# OpenTCUSandwich.net
KiCad netlist of a schematic drawn in EasyEDA
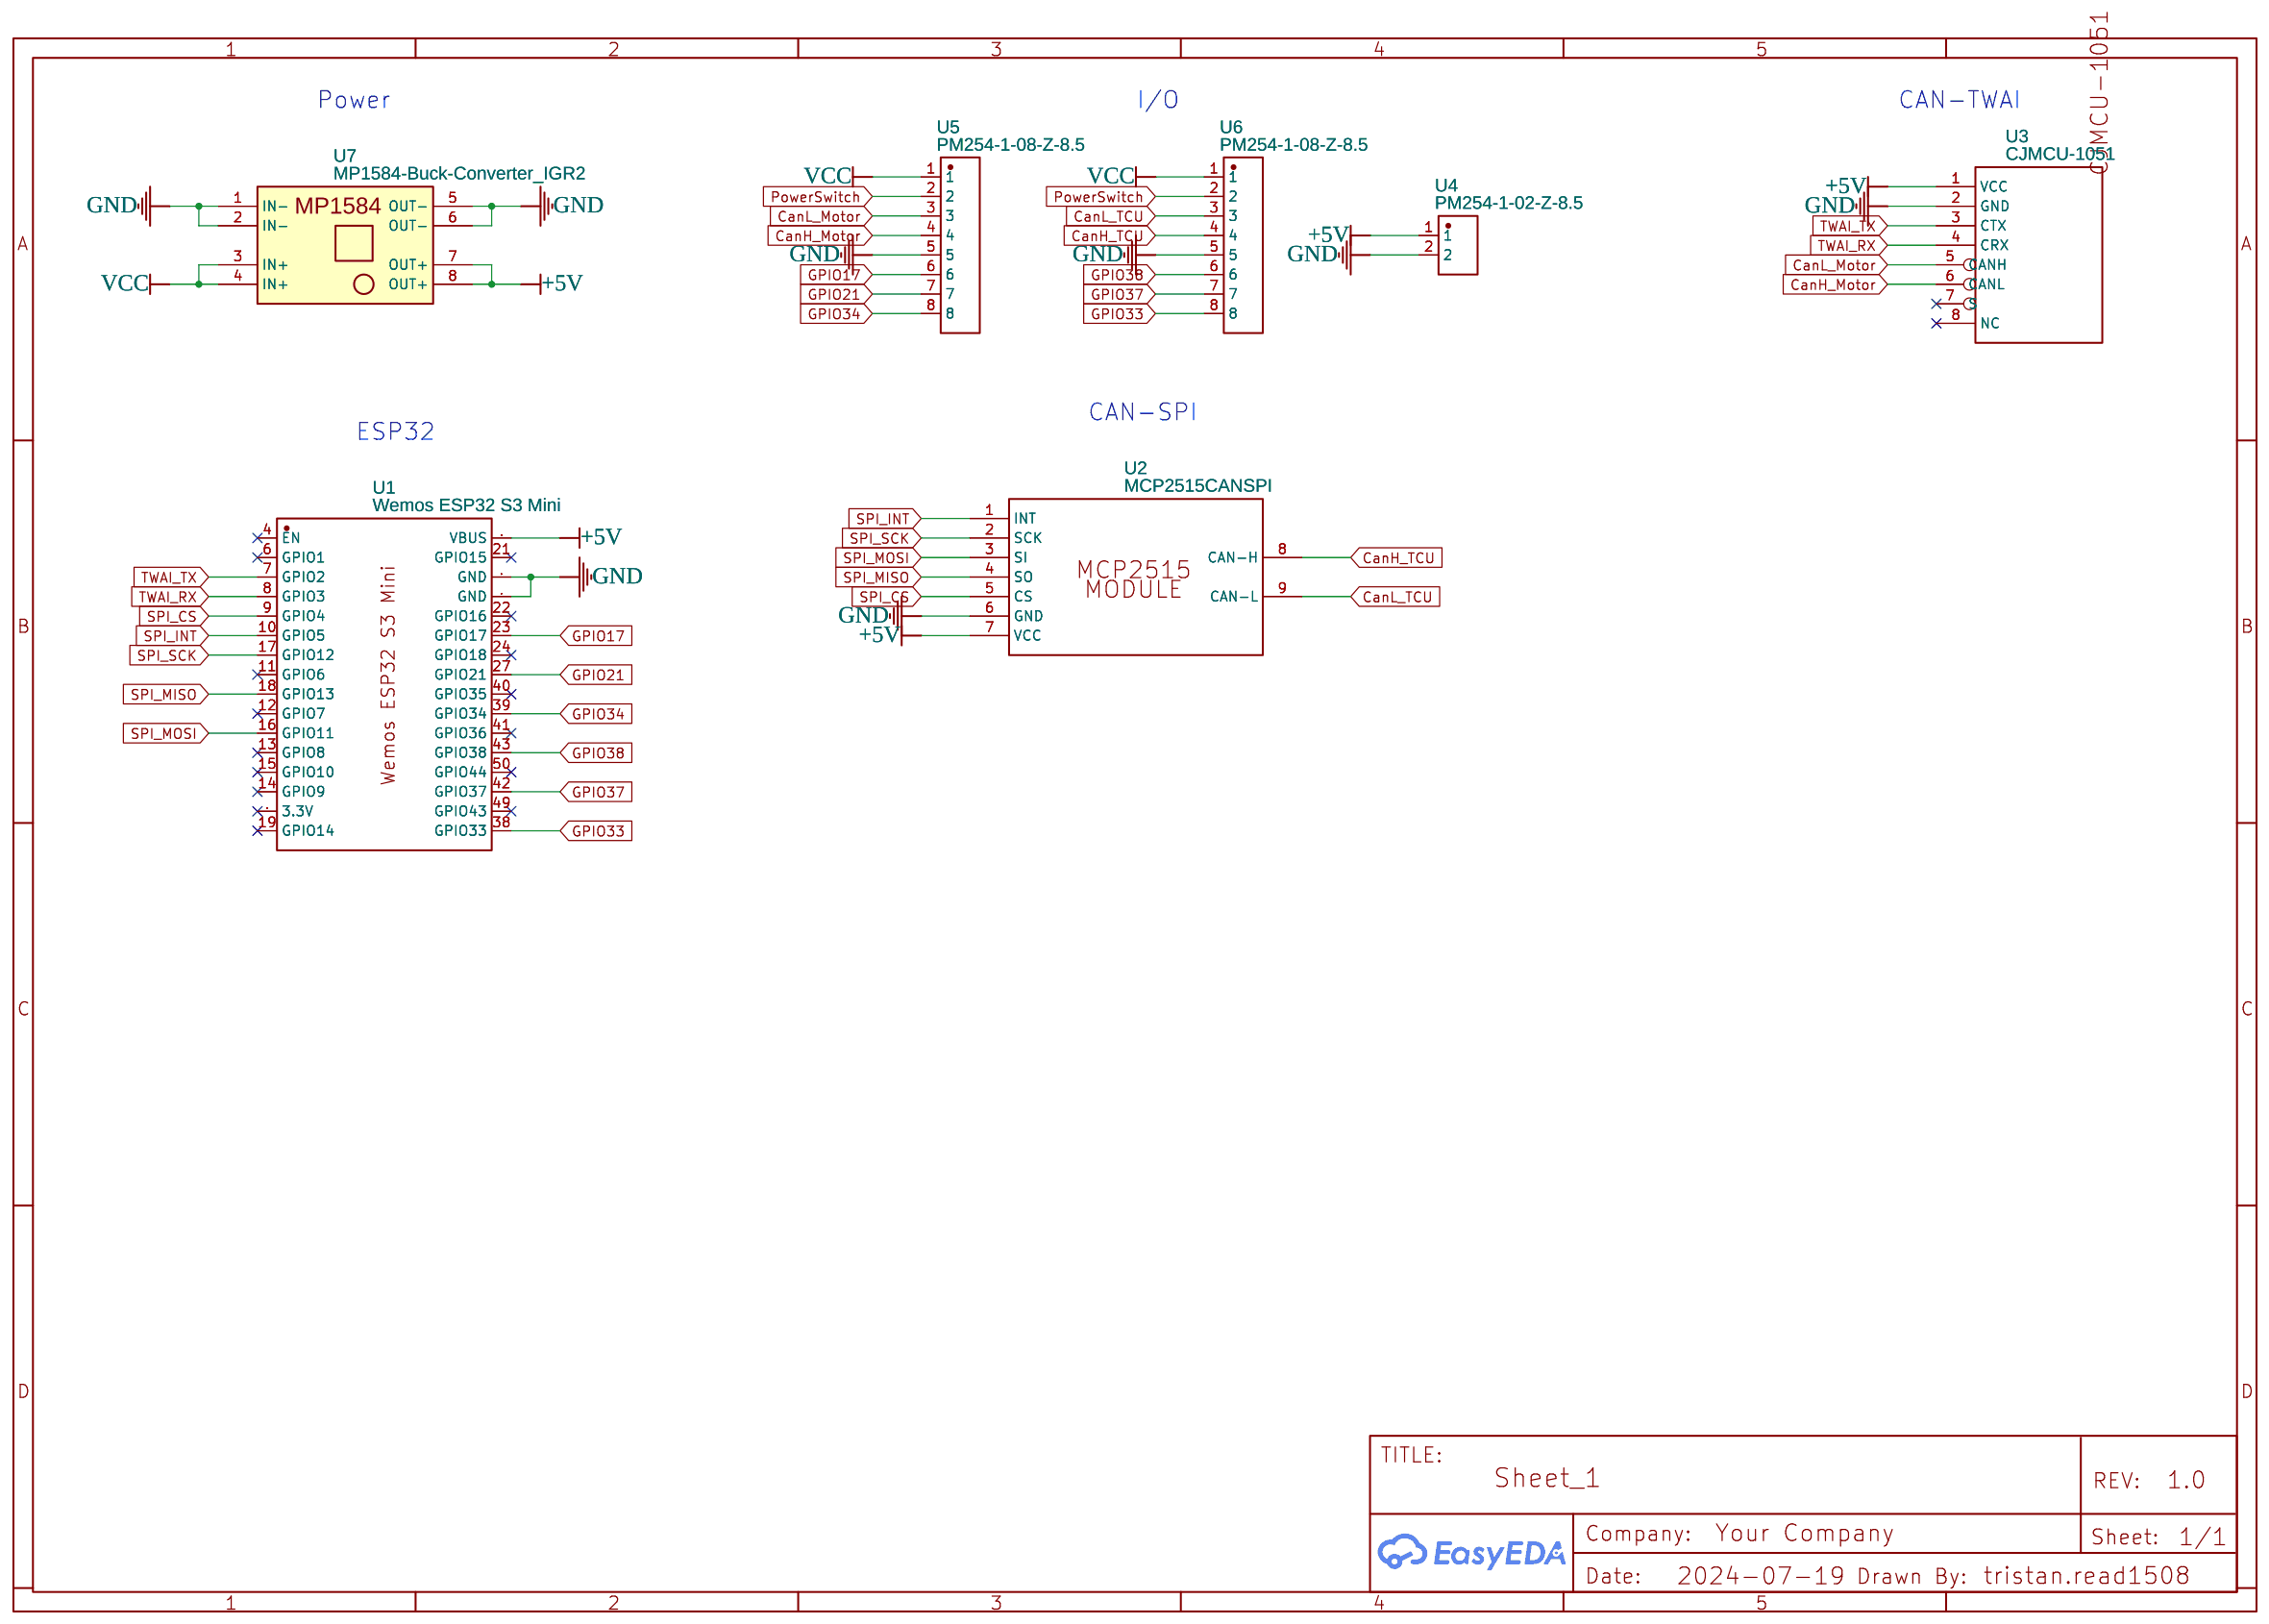
[diagram p0: schematic sheet]

(export (version "E")
  (design (tool "Eeschema 10.0.6"))
  (components
    (comp (ref "U1")
      (value "Wemos ESP32 S3 Mini")
      (fields (field (name "Manufacturer") "Wemos"))
      (libsource (lib "") (part "Wemos ESP32 S3 Mini"))
    )
    (comp (ref "U2") (value "MCP2515CANSPI") (libsource (lib "") (part "MCP2515CANSPI")))
    (comp (ref "U3") (value "CJMCU-1051") (libsource (lib "") (part "CJMCU-1051")))
    (comp (ref "U4")
      (value "PM254-1-02-Z-8.5")
      (fields (field (name "Manufacturer") "HCTL(华灿天禄)"))
      (libsource (lib "") (part "PM254-1-02-Z-8.5"))
    )
    (comp (ref "U5")
      (value "PM254-1-08-Z-8.5")
      (fields (field (name "Manufacturer") "HCTL(华灿天禄)"))
      (libsource (lib "") (part "PM254-1-08-Z-8.5"))
    )
    (comp (ref "U6")
      (value "PM254-1-08-Z-8.5")
      (fields (field (name "Manufacturer") "HCTL(华灿天禄)"))
      (libsource (lib "") (part "PM254-1-08-Z-8.5"))
    )
    (comp (ref "U7")
      (value "MP1584-Buck-Converter_IGR2")
      (fields (field (name "Manufacturer Part") "MP1584EN"))
      (libsource (lib "") (part "MP1584-Buck-Converter_IGR2"))
    )
  )
  (nets
    (net (code "1") (name "+5V") (class "Default")
      (node (ref "U1") (pin "5") (pinfunction "VBUS_5") (pintype "passive"))
      (node (ref "U2") (pin "7") (pinfunction "VCC_7") (pintype "unspecified"))
      (node (ref "U3") (pin "1") (pinfunction "VCC_1") (pintype "unspecified"))
      (node (ref "U4") (pin "1") (pinfunction "1_1") (pintype "unspecified"))
      (node (ref "U7") (pin "7") (pinfunction "OUT+_7") (pintype "unspecified"))
      (node (ref "U7") (pin "8") (pinfunction "OUT+_8") (pintype "unspecified"))
    )
    (net (code "2") (name "CanH_Motor") (class "Default")
      (node (ref "U3") (pin "6") (pinfunction "CANL_6") (pintype "unspecified"))
      (node (ref "U5") (pin "4") (pinfunction "4_4") (pintype "unspecified"))
    )
    (net (code "3") (name "CanH_TCU") (class "Default")
      (node (ref "U2") (pin "8") (pinfunction "CAN-H_8") (pintype "unspecified"))
      (node (ref "U6") (pin "4") (pinfunction "4_4") (pintype "unspecified"))
    )
    (net (code "4") (name "CanL_Motor") (class "Default")
      (node (ref "U3") (pin "5") (pinfunction "CANH_5") (pintype "unspecified"))
      (node (ref "U5") (pin "3") (pinfunction "3_3") (pintype "unspecified"))
    )
    (net (code "5") (name "CanL_TCU") (class "Default")
      (node (ref "U2") (pin "9") (pinfunction "CAN-L_9") (pintype "unspecified"))
      (node (ref "U6") (pin "3") (pinfunction "3_3") (pintype "unspecified"))
    )
    (net (code "6") (name "GND") (class "Default")
      (node (ref "U1") (pin "1") (pinfunction "GND_1") (pintype "unspecified"))
      (node (ref "U1") (pin "2") (pinfunction "GND_2") (pintype "unspecified"))
      (node (ref "U2") (pin "6") (pinfunction "GND_6") (pintype "unspecified"))
      (node (ref "U3") (pin "2") (pinfunction "GND_2") (pintype "unspecified"))
      (node (ref "U4") (pin "2") (pinfunction "2_2") (pintype "unspecified"))
      (node (ref "U5") (pin "5") (pinfunction "5_5") (pintype "unspecified"))
      (node (ref "U6") (pin "5") (pinfunction "5_5") (pintype "unspecified"))
      (node (ref "U7") (pin "1") (pinfunction "IN-_1") (pintype "unspecified"))
      (node (ref "U7") (pin "2") (pinfunction "IN-_2") (pintype "unspecified"))
      (node (ref "U7") (pin "5") (pinfunction "OUT-_5") (pintype "unspecified"))
      (node (ref "U7") (pin "6") (pinfunction "OUT-_6") (pintype "unspecified"))
    )
    (net (code "7") (name "GPIO17") (class "Default")
      (node (ref "U1") (pin "23") (pinfunction "GPIO17_23") (pintype "bidirectional"))
      (node (ref "U5") (pin "6") (pinfunction "6_6") (pintype "unspecified"))
    )
    (net (code "8") (name "GPIO21") (class "Default")
      (node (ref "U1") (pin "27") (pinfunction "GPIO21_27") (pintype "bidirectional"))
      (node (ref "U5") (pin "7") (pinfunction "7_7") (pintype "unspecified"))
    )
    (net (code "9") (name "GPIO33") (class "Default")
      (node (ref "U1") (pin "38") (pinfunction "GPIO33_38") (pintype "bidirectional"))
      (node (ref "U6") (pin "8") (pinfunction "8_8") (pintype "unspecified"))
    )
    (net (code "10") (name "GPIO34") (class "Default")
      (node (ref "U1") (pin "39") (pinfunction "GPIO34_39") (pintype "bidirectional"))
      (node (ref "U5") (pin "8") (pinfunction "8_8") (pintype "unspecified"))
    )
    (net (code "11") (name "GPIO37") (class "Default")
      (node (ref "U1") (pin "42") (pinfunction "GPIO37_42") (pintype "bidirectional"))
      (node (ref "U6") (pin "7") (pinfunction "7_7") (pintype "unspecified"))
    )
    (net (code "12") (name "GPIO38") (class "Default")
      (node (ref "U1") (pin "43") (pinfunction "GPIO38_43") (pintype "bidirectional"))
      (node (ref "U6") (pin "6") (pinfunction "6_6") (pintype "unspecified"))
    )
    (net (code "13") (name "PowerSwitch") (class "Default")
      (node (ref "U5") (pin "2") (pinfunction "2_2") (pintype "unspecified"))
      (node (ref "U6") (pin "2") (pinfunction "2_2") (pintype "unspecified"))
    )
    (net (code "14") (name "SPI_CS") (class "Default")
      (node (ref "U1") (pin "9") (pinfunction "GPIO4_9") (pintype "bidirectional"))
      (node (ref "U2") (pin "5") (pinfunction "CS_5") (pintype "unspecified"))
    )
    (net (code "15") (name "SPI_INT") (class "Default")
      (node (ref "U1") (pin "10") (pinfunction "GPIO5_10") (pintype "bidirectional"))
      (node (ref "U2") (pin "1") (pinfunction "INT_1") (pintype "unspecified"))
    )
    (net (code "16") (name "SPI_MISO") (class "Default")
      (node (ref "U1") (pin "18") (pinfunction "GPIO13_18") (pintype "bidirectional"))
      (node (ref "U2") (pin "4") (pinfunction "SO_4") (pintype "unspecified"))
    )
    (net (code "17") (name "SPI_MOSI") (class "Default")
      (node (ref "U1") (pin "16") (pinfunction "GPIO11_16") (pintype "bidirectional"))
      (node (ref "U2") (pin "3") (pinfunction "SI_3") (pintype "unspecified"))
    )
    (net (code "18") (name "SPI_SCK") (class "Default")
      (node (ref "U1") (pin "17") (pinfunction "GPIO12_17") (pintype "bidirectional"))
      (node (ref "U2") (pin "2") (pinfunction "SCK_2") (pintype "unspecified"))
    )
    (net (code "19") (name "TWAI_RX") (class "Default")
      (node (ref "U1") (pin "8") (pinfunction "GPIO3_8") (pintype "bidirectional"))
      (node (ref "U3") (pin "4") (pinfunction "CRX_4") (pintype "unspecified"))
    )
    (net (code "20") (name "TWAI_TX") (class "Default")
      (node (ref "U1") (pin "7") (pinfunction "GPIO2_7") (pintype "bidirectional"))
      (node (ref "U3") (pin "3") (pinfunction "CTX_3") (pintype "unspecified"))
    )
    (net (code "21") (name "VCC") (class "Default")
      (node (ref "U5") (pin "1") (pinfunction "1_1") (pintype "unspecified"))
      (node (ref "U6") (pin "1") (pinfunction "1_1") (pintype "unspecified"))
      (node (ref "U7") (pin "3") (pinfunction "IN+_3") (pintype "unspecified"))
      (node (ref "U7") (pin "4") (pinfunction "IN+_4") (pintype "unspecified"))
    )
    (net (code "22") (name "unconnected-(U1-3.3V-Pad3)") (class "Default")
      (node (ref "U1") (pin "3") (pinfunction "3.3V_3") (pintype "passive+no_connect"))
    )
    (net (code "23") (name "unconnected-(U1-EN-Pad4)") (class "Default")
      (node (ref "U1") (pin "4") (pinfunction "EN_4") (pintype "unspecified+no_connect"))
    )
    (net (code "24") (name "unconnected-(U1-GPIO1-Pad6)") (class "Default")
      (node (ref "U1") (pin "6") (pinfunction "GPIO1_6") (pintype "bidirectional+no_connect"))
    )
    (net (code "25") (name "unconnected-(U1-GPIO6-Pad11)") (class "Default")
      (node (ref "U1") (pin "11") (pinfunction "GPIO6_11") (pintype "bidirectional+no_connect"))
    )
    (net (code "26") (name "unconnected-(U1-GPIO7-Pad12)") (class "Default")
      (node (ref "U1") (pin "12") (pinfunction "GPIO7_12") (pintype "bidirectional+no_connect"))
    )
    (net (code "27") (name "unconnected-(U1-GPIO8-Pad13)") (class "Default")
      (node (ref "U1") (pin "13") (pinfunction "GPIO8_13") (pintype "bidirectional+no_connect"))
    )
    (net (code "28") (name "unconnected-(U1-GPIO9-Pad14)") (class "Default")
      (node (ref "U1") (pin "14") (pinfunction "GPIO9_14") (pintype "bidirectional+no_connect"))
    )
    (net (code "29") (name "unconnected-(U1-GPIO10-Pad15)") (class "Default")
      (node (ref "U1") (pin "15") (pinfunction "GPIO10_15") (pintype "bidirectional+no_connect"))
    )
    (net (code "30") (name "unconnected-(U1-GPIO14-Pad19)") (class "Default")
      (node (ref "U1") (pin "19") (pinfunction "GPIO14_19") (pintype "bidirectional+no_connect"))
    )
    (net (code "31") (name "unconnected-(U1-GPIO15-Pad21)") (class "Default")
      (node (ref "U1") (pin "21") (pinfunction "GPIO15_21") (pintype "bidirectional+no_connect"))
    )
    (net (code "32") (name "unconnected-(U1-GPIO16-Pad22)") (class "Default")
      (node (ref "U1") (pin "22") (pinfunction "GPIO16_22") (pintype "bidirectional+no_connect"))
    )
    (net (code "33") (name "unconnected-(U1-GPIO18-Pad24)") (class "Default")
      (node (ref "U1") (pin "24") (pinfunction "GPIO18_24") (pintype "bidirectional+no_connect"))
    )
    (net (code "34") (name "unconnected-(U1-GPIO35-Pad40)") (class "Default")
      (node (ref "U1") (pin "40") (pinfunction "GPIO35_40") (pintype "bidirectional+no_connect"))
    )
    (net (code "35") (name "unconnected-(U1-GPIO36-Pad41)") (class "Default")
      (node (ref "U1") (pin "41") (pinfunction "GPIO36_41") (pintype "bidirectional+no_connect"))
    )
    (net (code "36") (name "unconnected-(U1-GPIO43-Pad49)") (class "Default")
      (node (ref "U1") (pin "49") (pinfunction "GPIO43_49") (pintype "bidirectional+no_connect"))
    )
    (net (code "37") (name "unconnected-(U1-GPIO44-Pad50)") (class "Default")
      (node (ref "U1") (pin "50") (pinfunction "GPIO44_50") (pintype "bidirectional+no_connect"))
    )
    (net (code "38") (name "unconnected-(U3-NC-Pad8)") (class "Default")
      (node (ref "U3") (pin "8") (pinfunction "NC_8") (pintype "unspecified+no_connect"))
    )
    (net (code "39") (name "unconnected-(U3-S-Pad7)") (class "Default")
      (node (ref "U3") (pin "7") (pinfunction "S_7") (pintype "unspecified+no_connect"))
    )
  )
)
